# UCC28180_PFC_Controller.net
KiCad netlist of a schematic drawn in Altium Designer
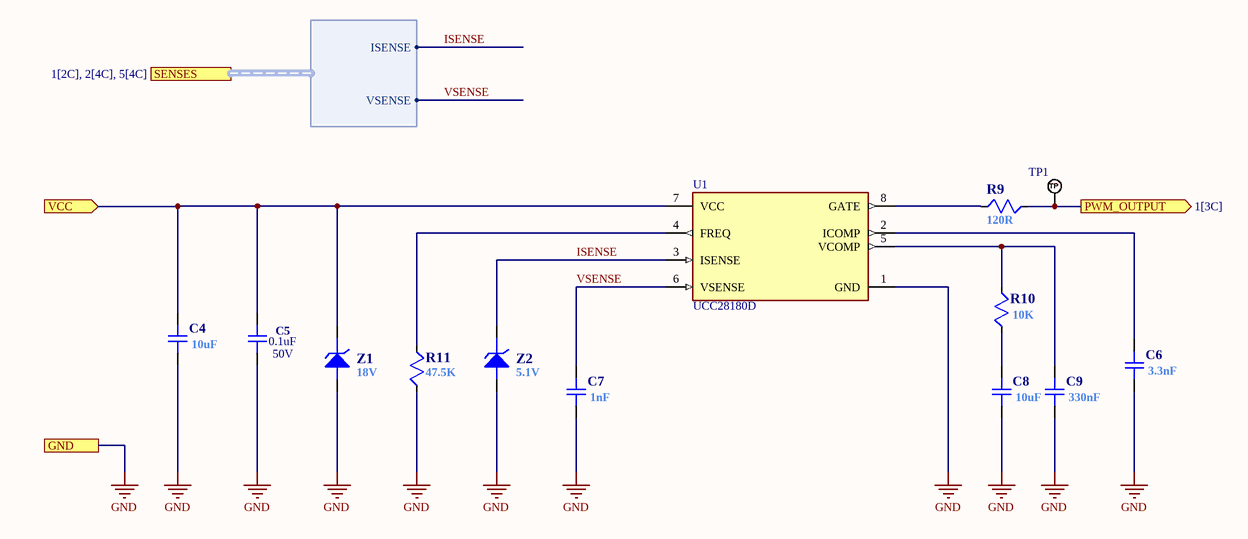
[diagram p0: UCC28180_PFC_Controller.SchDoc]

(export (version "E")
  (design (tool "Eeschema 10.0.6"))
  (components
    (comp (ref "C4")
      (value "10uF")
      (footprint "CAP_0805")
      (description "MLCC (2012) 0805 10uF 25VDC ±10% X5R")
      (fields
        (field (name "MANUFACTURER") "YAGEO")
        (field (name "MANUFACTURER PART NUMBER") "CC0805KKX7R9BB105")
      )
      (libsource (lib "Phil-lab") (part "CAP_0805"))
    )
    (comp (ref "C5")
      (value "0.1uF")
      (footprint "CAPC1608N")
      (description "MLCC (1608) 0603 100nF 50VDC ±10% X7R")
      (fields (field (name "RATING") "50V") (field (name "Comment") "CL10B104KB8NNNC"))
      (libsource (lib "WG_MainBoard_NV2") (part "CAP_0805"))
    )
    (comp (ref "C6")
      (value "3.3nF")
      (footprint "CAP_0805")
      (description "MLCC (1608) 0603 3.3nF 50VDC ±10% X7R")
      (fields
        (field (name "MANUFACTURER") "YAGEO")
        (field (name "MANUFACTURER PART NUMBER") "CC0805KKX7R9BB105")
      )
      (libsource (lib "Phil-lab") (part "CAP_0805"))
    )
    (comp (ref "C7")
      (value "1nF")
      (footprint "CAP_0805")
      (description "MLCC (1608) 0603 1nF 50VDC ±10% X7R")
      (fields
        (field (name "MANUFACTURER") "YAGEO")
        (field (name "MANUFACTURER PART NUMBER") "CC0805KKX7R9BB105")
      )
      (libsource (lib "Phil-lab") (part "CAP_0805"))
    )
    (comp (ref "C8")
      (value "10uF")
      (footprint "CAP_0805")
      (description "MLCC (2012) 0805 10uF 25VDC ±10% X5R")
      (fields
        (field (name "MANUFACTURER") "YAGEO")
        (field (name "MANUFACTURER PART NUMBER") "CC0805KKX7R9BB105")
      )
      (libsource (lib "Phil-lab") (part "CAP_0805"))
    )
    (comp (ref "C9")
      (value "330nF")
      (footprint "CAP_0805")
      (description "MLCC (1608) 0603 330nF 25VDC -20% +80% Y5V")
      (fields
        (field (name "MANUFACTURER") "YAGEO")
        (field (name "MANUFACTURER PART NUMBER") "CC0805KKX7R9BB105")
      )
      (libsource (lib "Phil-lab") (part "CAP_0805"))
    )
    (comp (ref "R9")
      (value "120R")
      (footprint "PCB_EZ_BuckPowerDriver V2.0:RESC1608N")
      (description "RES.(1608) 0603 120 Ohms 5% 1/10W-S 100PPM")
      (fields (field (name "Comment") "CRT03J7E1200"))
      (libsource (lib "WG_MainBoard_NV1") (part "RES"))
    )
    (comp (ref "R10")
      (value "10K")
      (footprint "PCB_EZ_BuckPowerDriver V2.0:RESC1608N")
      (description "RES.(1608) 0603 10K Ohms 5% 1/10W 100PPM SMT")
      (fields (field (name "Comment") "RC0603JR-0710KL"))
      (libsource (lib "WG_MainBoard_NV1") (part "RES"))
    )
    (comp (ref "R11")
      (value "47.5K")
      (footprint "PCB_EZ_BuckPowerDriver V2.0:RESC1608N")
      (description "RES.(1608) 0603 47.5K Ohms 1% 1/10W-S 100PPM")
      (fields (field (name "Comment") "0603SAF4752T5E"))
      (libsource (lib "WG_MainBoard_NV1") (part "RES"))
    )
    (comp (ref "TP1")
      (value "TP_NOBOM")
      (footprint "PAD_RND_1MM")
      (description "Test Point Round 1mm (NO BOM)")
      (libsource (lib "Phil-lab") (part "TEST_POINT_RND_1MM"))
    )
    (comp (ref "U1")
      (value "UCC28180D")
      (footprint "FP-D0008A-MFG")
      (description "IC PFC CTRLR AVERAGE CURR 8SOIC")
      (fields
        (field (name "OCTOPART") "https://octopart.com/ucc28180d-texas+instruments-31566950")
        (field (name "MANUFACTURER") "Texas Instruments")
      )
      (libsource (lib "Altium Content Vault") (part "c95dd6f63eea92a43b6a1c8dc0b98c9"))
    )
    (comp (ref "Z1")
      (value "18V")
      (footprint "SOD523C")
      (description "DIODE ZENER 500mW 18V ±5% SOD123 SMT")
      (fields (field (name "Comment") "MMSZ18V-HT"))
      (libsource (lib "Components") (part "ZENER-1"))
    )
    (comp (ref "Z2")
      (value "5.1V")
      (footprint "SOD523C")
      (description "Zener Diode 5.1 V 300 mW ±6% Surface Mount SOD-523")
      (fields (field (name "Comment") "BZT52C5V1TQ-7-F"))
      (libsource (lib "Components") (part "ZENER-1"))
    )
  )
  (nets
    (net (code "2") (name "/ISENSE") (class "Default")
      (node (ref "U1") (pin "3") (pinfunction "ISENSE_3") (pintype "input"))
      (node (ref "Z2") (pin "2") (pinfunction "K_2") (pintype "passive"))
    )
    (net (code "3") (name "/PWM_OUTPUT") (class "Default")
      (node (ref "R9") (pin "2") (pinfunction "2_2") (pintype "passive"))
      (node (ref "TP1") (pin "1") (pinfunction "TP_1") (pintype "passive"))
    )
    (net (code "4") (name "/VCC") (class "Default")
      (node (ref "C4") (pin "2") (pinfunction "2_2") (pintype "passive"))
      (node (ref "C5") (pin "2") (pinfunction "2_2") (pintype "passive"))
      (node (ref "U1") (pin "7") (pinfunction "VCC_7") (pintype "power_in"))
      (node (ref "Z1") (pin "2") (pinfunction "K_2") (pintype "passive"))
    )
    (net (code "5") (name "/VSENSE") (class "Default")
      (node (ref "C7") (pin "2") (pinfunction "2_2") (pintype "passive"))
      (node (ref "U1") (pin "6") (pinfunction "VSENSE_6") (pintype "input"))
    )
    (net (code "7") (name "GND") (class "Default")
      (node (ref "C4") (pin "1") (pinfunction "1_1") (pintype "passive"))
      (node (ref "C5") (pin "1") (pinfunction "1_1") (pintype "passive"))
      (node (ref "C6") (pin "1") (pinfunction "1_1") (pintype "passive"))
      (node (ref "C7") (pin "1") (pinfunction "1_1") (pintype "passive"))
      (node (ref "C8") (pin "1") (pinfunction "1_1") (pintype "passive"))
      (node (ref "C9") (pin "1") (pinfunction "1_1") (pintype "passive"))
      (node (ref "R11") (pin "1") (pinfunction "1_1") (pintype "passive"))
      (node (ref "U1") (pin "1") (pinfunction "GND_1") (pintype "power_in"))
      (node (ref "Z1") (pin "1") (pinfunction "A_1") (pintype "passive"))
      (node (ref "Z2") (pin "1") (pinfunction "A_1") (pintype "passive"))
    )
    (net (code "8") (name "Net-(C8-Pad2)") (class "Default")
      (node (ref "C8") (pin "2") (pinfunction "2_2") (pintype "passive"))
      (node (ref "R10") (pin "2") (pinfunction "2_2") (pintype "passive"))
    )
    (net (code "9") (name "Net-(U1-FREQ)") (class "Default")
      (node (ref "R11") (pin "2") (pinfunction "2_2") (pintype "passive"))
      (node (ref "U1") (pin "4") (pinfunction "FREQ_4") (pintype "output"))
    )
    (net (code "10") (name "Net-(U1-GATE)") (class "Default")
      (node (ref "R9") (pin "1") (pinfunction "1_1") (pintype "passive"))
      (node (ref "U1") (pin "8") (pinfunction "GATE_8") (pintype "output"))
    )
    (net (code "11") (name "Net-(U1-ICOMP)") (class "Default")
      (node (ref "C6") (pin "2") (pinfunction "2_2") (pintype "passive"))
      (node (ref "U1") (pin "2") (pinfunction "ICOMP_2") (pintype "output"))
    )
    (net (code "12") (name "Net-(U1-VCOMP)") (class "Default")
      (node (ref "C9") (pin "2") (pinfunction "2_2") (pintype "passive"))
      (node (ref "R10") (pin "1") (pinfunction "1_1") (pintype "passive"))
      (node (ref "U1") (pin "5") (pinfunction "VCOMP_5") (pintype "output"))
    )
  )
)
